# ETRX_RECU.net
KiCad netlist of a schematic drawn in Altium Designer
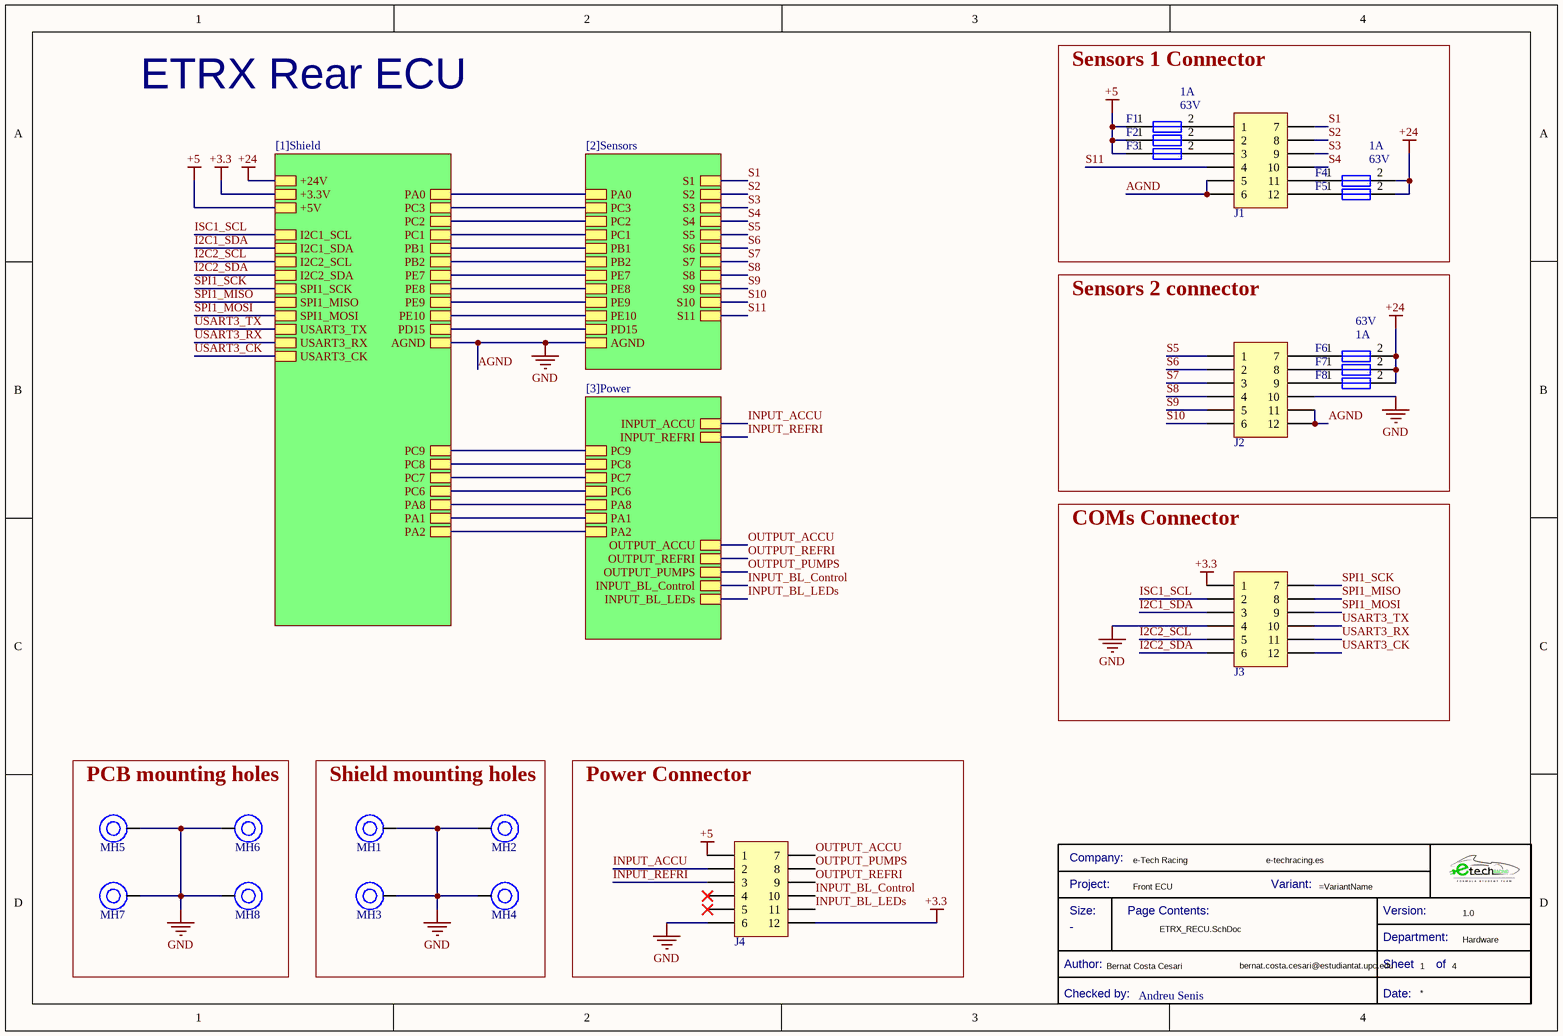
[diagram p0: ETRX_RECU.SchDoc]

(export (version "E")
  (design (tool "Eeschema 10.0.6"))
  (components
    (comp (ref "F1")
      (value "0437001.WRA")
      (footprint "Fuse_1206")
      (description "Fuse Chip Fast Acting 1A 63V SMD Solder Pad 1206 Ceramic T/R Automotive")
      (fields
        (field (name "MANUFACTURER") "Littelfuse")
        (field (name "CURRENT RATING") "1A")
        (field (name "VOLTAGE RATING (DC)") "63V")
        (field (name ".CREATOR") "DO")
      )
      (libsource (lib "Filter components") (part "Fuse_1A_63V_1206"))
    )
    (comp (ref "F2")
      (value "0437001.WRA")
      (footprint "Fuse_1206")
      (description "Fuse Chip Fast Acting 1A 63V SMD Solder Pad 1206 Ceramic T/R Automotive")
      (fields (field (name "MANUFACTURER") "Littelfuse") (field (name ".CREATOR") "DO"))
      (libsource (lib "Filter components") (part "Fuse_1A_63V_1206"))
    )
    (comp (ref "F3")
      (value "0437001.WRA")
      (footprint "Fuse_1206")
      (description "Fuse Chip Fast Acting 1A 63V SMD Solder Pad 1206 Ceramic T/R Automotive")
      (fields (field (name "MANUFACTURER") "Littelfuse") (field (name ".CREATOR") "DO"))
      (libsource (lib "Filter components") (part "Fuse_1A_63V_1206"))
    )
    (comp (ref "F4")
      (value "0437001.WRA")
      (footprint "Fuse_1206")
      (description "Fuse Chip Fast Acting 1A 63V SMD Solder Pad 1206 Ceramic T/R Automotive")
      (fields
        (field (name "MANUFACTURER") "Littelfuse")
        (field (name "CURRENT RATING") "1A")
        (field (name "VOLTAGE RATING (DC)") "63V")
        (field (name ".CREATOR") "DO")
      )
      (libsource (lib "Filter components") (part "Fuse_1A_63V_1206"))
    )
    (comp (ref "F5")
      (value "0437001.WRA")
      (footprint "Fuse_1206")
      (description "Fuse Chip Fast Acting 1A 63V SMD Solder Pad 1206 Ceramic T/R Automotive")
      (fields (field (name "MANUFACTURER") "Littelfuse") (field (name ".CREATOR") "DO"))
      (libsource (lib "Filter components") (part "Fuse_1A_63V_1206"))
    )
    (comp (ref "F6")
      (value "0437001.WRA")
      (footprint "Fuse_1206")
      (description "Fuse Chip Fast Acting 1A 63V SMD Solder Pad 1206 Ceramic T/R Automotive")
      (fields
        (field (name "MANUFACTURER") "Littelfuse")
        (field (name "CURRENT RATING") "1A")
        (field (name "VOLTAGE RATING (DC)") "63V")
        (field (name ".CREATOR") "DO")
      )
      (libsource (lib "Filter components") (part "Fuse_1A_63V_1206"))
    )
    (comp (ref "F7")
      (value "0437001.WRA")
      (footprint "Fuse_1206")
      (description "Fuse Chip Fast Acting 1A 63V SMD Solder Pad 1206 Ceramic T/R Automotive")
      (fields (field (name "MANUFACTURER") "Littelfuse") (field (name ".CREATOR") "DO"))
      (libsource (lib "Filter components") (part "Fuse_1A_63V_1206"))
    )
    (comp (ref "F8")
      (value "0437001.WRA")
      (footprint "Fuse_1206")
      (description "Fuse Chip Fast Acting 1A 63V SMD Solder Pad 1206 Ceramic T/R Automotive")
      (fields (field (name "MANUFACTURER") "Littelfuse") (field (name ".CREATOR") "DO"))
      (libsource (lib "Filter components") (part "Fuse_1A_63V_1206"))
    )
    (comp (ref "J1")
      (value "1053101112")
      (footprint "J_NanoFit_2x6_V")
      (libsource (lib "Electromechanical") (part "J_NanoFit_2x6_V"))
    )
    (comp (ref "J2")
      (value "1053101112")
      (footprint "J_NanoFit_2x6_V")
      (libsource (lib "Electromechanical") (part "J_NanoFit_2x6_V"))
    )
    (comp (ref "J3")
      (value "1053101112")
      (footprint "J_NanoFit_2x6_V")
      (libsource (lib "Electromechanical") (part "J_NanoFit_2x6_V"))
    )
    (comp (ref "J4")
      (value "1053101112")
      (footprint "J_NanoFit_2x6_V")
      (libsource (lib "Electromechanical") (part "J_NanoFit_2x6_V"))
    )
    (comp (ref "MH1")
      (value "Mounting_Hole_M3")
      (footprint "Mounting_Hole_M3")
      (libsource (lib "Electromechanical") (part "Mounting_Hole_M3"))
    )
    (comp (ref "MH2")
      (value "Mounting_Hole_M3")
      (footprint "Mounting_Hole_M3")
      (libsource (lib "Electromechanical") (part "Mounting_Hole_M3"))
    )
    (comp (ref "MH3")
      (value "Mounting_Hole_M3")
      (footprint "Mounting_Hole_M3")
      (libsource (lib "Electromechanical") (part "Mounting_Hole_M3"))
    )
    (comp (ref "MH4")
      (value "Mounting_Hole_M3")
      (footprint "Mounting_Hole_M3")
      (libsource (lib "Electromechanical") (part "Mounting_Hole_M3"))
    )
    (comp (ref "MH5")
      (value "Mounting_Hole_M4")
      (footprint "Mounting_Hole_M4")
      (libsource (lib "Electromechanical") (part "Mounting_Hole_M4"))
    )
    (comp (ref "MH6")
      (value "Mounting_Hole_M4")
      (footprint "Mounting_Hole_M4")
      (libsource (lib "Electromechanical") (part "Mounting_Hole_M4"))
    )
    (comp (ref "MH7")
      (value "Mounting_Hole_M4")
      (footprint "Mounting_Hole_M4")
      (libsource (lib "Electromechanical") (part "Mounting_Hole_M4"))
    )
    (comp (ref "MH8")
      (value "Mounting_Hole_M4")
      (footprint "Mounting_Hole_M4")
      (libsource (lib "Electromechanical") (part "Mounting_Hole_M4"))
    )
  )
  (nets
    (net (code "1") (name "+3.3") (class "Default")
      (node (ref "J3") (pin "1") (pinfunction "1_1") (pintype "passive"))
      (node (ref "J4") (pin "12") (pinfunction "12_12") (pintype "passive"))
    )
    (net (code "2") (name "+5") (class "Default")
      (node (ref "F1") (pin "1") (pinfunction "1_1") (pintype "passive"))
      (node (ref "F2") (pin "1") (pinfunction "1_1") (pintype "passive"))
      (node (ref "F3") (pin "1") (pinfunction "1_1") (pintype "passive"))
      (node (ref "J4") (pin "1") (pinfunction "1_1") (pintype "passive"))
    )
    (net (code "3") (name "+24") (class "Default")
      (node (ref "F4") (pin "2") (pinfunction "2_2") (pintype "passive"))
      (node (ref "F5") (pin "2") (pinfunction "2_2") (pintype "passive"))
      (node (ref "F6") (pin "2") (pinfunction "2_2") (pintype "passive"))
      (node (ref "F7") (pin "2") (pinfunction "2_2") (pintype "passive"))
      (node (ref "F8") (pin "2") (pinfunction "2_2") (pintype "passive"))
    )
    (net (code "4") (name "/I2C1_SDA") (class "Default")
      (node (ref "J3") (pin "3") (pinfunction "3_3") (pintype "passive"))
    )
    (net (code "5") (name "/I2C2_SCL") (class "Default")
      (node (ref "J3") (pin "5") (pinfunction "5_5") (pintype "passive"))
    )
    (net (code "6") (name "/I2C2_SDA") (class "Default")
      (node (ref "J3") (pin "6") (pinfunction "6_6") (pintype "passive"))
    )
    (net (code "7") (name "/INPUT_ACCU") (class "Default")
      (node (ref "J4") (pin "2") (pinfunction "2_2") (pintype "passive"))
    )
    (net (code "8") (name "/INPUT_BL_Control") (class "Default")
      (node (ref "J4") (pin "10") (pinfunction "10_10") (pintype "passive"))
    )
    (net (code "9") (name "/INPUT_BL_LEDs") (class "Default")
      (node (ref "J4") (pin "11") (pinfunction "11_11") (pintype "passive"))
    )
    (net (code "10") (name "/INPUT_REFRI") (class "Default")
      (node (ref "J4") (pin "3") (pinfunction "3_3") (pintype "passive"))
    )
    (net (code "11") (name "/ISC1_SCL") (class "Default")
      (node (ref "J3") (pin "2") (pinfunction "2_2") (pintype "passive"))
    )
    (net (code "12") (name "/OUTPUT_ACCU") (class "Default")
      (node (ref "J4") (pin "7") (pinfunction "7_7") (pintype "passive"))
    )
    (net (code "13") (name "/OUTPUT_PUMPS") (class "Default")
      (node (ref "J4") (pin "8") (pinfunction "8_8") (pintype "passive"))
    )
    (net (code "14") (name "/OUTPUT_REFRI") (class "Default")
      (node (ref "J4") (pin "9") (pinfunction "9_9") (pintype "passive"))
    )
    (net (code "33") (name "/S1") (class "Default")
      (node (ref "J1") (pin "7") (pinfunction "7_7") (pintype "passive"))
    )
    (net (code "34") (name "/S2") (class "Default")
      (node (ref "J1") (pin "8") (pinfunction "8_8") (pintype "passive"))
    )
    (net (code "35") (name "/S3") (class "Default")
      (node (ref "J1") (pin "9") (pinfunction "9_9") (pintype "passive"))
    )
    (net (code "36") (name "/S4") (class "Default")
      (node (ref "J1") (pin "10") (pinfunction "10_10") (pintype "passive"))
    )
    (net (code "37") (name "/S5") (class "Default")
      (node (ref "J2") (pin "1") (pinfunction "1_1") (pintype "passive"))
    )
    (net (code "38") (name "/S6") (class "Default")
      (node (ref "J2") (pin "2") (pinfunction "2_2") (pintype "passive"))
    )
    (net (code "39") (name "/S7") (class "Default")
      (node (ref "J2") (pin "3") (pinfunction "3_3") (pintype "passive"))
    )
    (net (code "40") (name "/S8") (class "Default")
      (node (ref "J2") (pin "4") (pinfunction "4_4") (pintype "passive"))
    )
    (net (code "41") (name "/S9") (class "Default")
      (node (ref "J2") (pin "5") (pinfunction "5_5") (pintype "passive"))
    )
    (net (code "42") (name "/S10") (class "Default")
      (node (ref "J2") (pin "6") (pinfunction "6_6") (pintype "passive"))
    )
    (net (code "43") (name "/S11") (class "Default")
      (node (ref "J1") (pin "4") (pinfunction "4_4") (pintype "passive"))
    )
    (net (code "44") (name "/SPI1_MISO") (class "Default")
      (node (ref "J3") (pin "8") (pinfunction "8_8") (pintype "passive"))
    )
    (net (code "45") (name "/SPI1_MOSI") (class "Default")
      (node (ref "J3") (pin "9") (pinfunction "9_9") (pintype "passive"))
    )
    (net (code "46") (name "/SPI1_SCK") (class "Default")
      (node (ref "J3") (pin "7") (pinfunction "7_7") (pintype "passive"))
    )
    (net (code "47") (name "/USART3_CK") (class "Default")
      (node (ref "J3") (pin "12") (pinfunction "12_12") (pintype "passive"))
    )
    (net (code "48") (name "/USART3_RX") (class "Default")
      (node (ref "J3") (pin "11") (pinfunction "11_11") (pintype "passive"))
    )
    (net (code "49") (name "/USART3_TX") (class "Default")
      (node (ref "J3") (pin "10") (pinfunction "10_10") (pintype "passive"))
    )
    (net (code "50") (name "GND") (class "Default")
      (node (ref "J1") (pin "5") (pinfunction "5_5") (pintype "passive"))
      (node (ref "J1") (pin "6") (pinfunction "6_6") (pintype "passive"))
      (node (ref "J2") (pin "10") (pinfunction "10_10") (pintype "passive"))
      (node (ref "J2") (pin "11") (pinfunction "11_11") (pintype "passive"))
      (node (ref "J2") (pin "12") (pinfunction "12_12") (pintype "passive"))
      (node (ref "J3") (pin "4") (pinfunction "4_4") (pintype "passive"))
      (node (ref "J4") (pin "6") (pinfunction "6_6") (pintype "passive"))
      (node (ref "MH1") (pin "1") (pinfunction "1_1") (pintype "passive"))
      (node (ref "MH2") (pin "1") (pinfunction "1_1") (pintype "passive"))
      (node (ref "MH3") (pin "1") (pinfunction "1_1") (pintype "passive"))
      (node (ref "MH4") (pin "1") (pinfunction "1_1") (pintype "passive"))
      (node (ref "MH5") (pin "1") (pinfunction "1_1") (pintype "passive"))
      (node (ref "MH6") (pin "1") (pinfunction "1_1") (pintype "passive"))
      (node (ref "MH7") (pin "1") (pinfunction "1_1") (pintype "passive"))
      (node (ref "MH8") (pin "1") (pinfunction "1_1") (pintype "passive"))
    )
    (net (code "51") (name "Net-(F1-Pad2)") (class "Default")
      (node (ref "F1") (pin "2") (pinfunction "2_2") (pintype "passive"))
      (node (ref "J1") (pin "1") (pinfunction "1_1") (pintype "passive"))
    )
    (net (code "52") (name "Net-(F2-Pad2)") (class "Default")
      (node (ref "F2") (pin "2") (pinfunction "2_2") (pintype "passive"))
      (node (ref "J1") (pin "2") (pinfunction "2_2") (pintype "passive"))
    )
    (net (code "53") (name "Net-(F3-Pad2)") (class "Default")
      (node (ref "F3") (pin "2") (pinfunction "2_2") (pintype "passive"))
      (node (ref "J1") (pin "3") (pinfunction "3_3") (pintype "passive"))
    )
    (net (code "54") (name "Net-(F4-Pad1)") (class "Default")
      (node (ref "F4") (pin "1") (pinfunction "1_1") (pintype "passive"))
      (node (ref "J1") (pin "11") (pinfunction "11_11") (pintype "passive"))
    )
    (net (code "55") (name "Net-(F5-Pad1)") (class "Default")
      (node (ref "F5") (pin "1") (pinfunction "1_1") (pintype "passive"))
      (node (ref "J1") (pin "12") (pinfunction "12_12") (pintype "passive"))
    )
    (net (code "56") (name "Net-(F6-Pad1)") (class "Default")
      (node (ref "F6") (pin "1") (pinfunction "1_1") (pintype "passive"))
      (node (ref "J2") (pin "7") (pinfunction "7_7") (pintype "passive"))
    )
    (net (code "57") (name "Net-(F7-Pad1)") (class "Default")
      (node (ref "F7") (pin "1") (pinfunction "1_1") (pintype "passive"))
      (node (ref "J2") (pin "8") (pinfunction "8_8") (pintype "passive"))
    )
    (net (code "58") (name "Net-(F8-Pad1)") (class "Default")
      (node (ref "F8") (pin "1") (pinfunction "1_1") (pintype "passive"))
      (node (ref "J2") (pin "9") (pinfunction "9_9") (pintype "passive"))
    )
    (net (code "59") (name "unconnected-(J4-Pad4)") (class "Default")
      (node (ref "J4") (pin "4") (pinfunction "4_4") (pintype "passive+no_connect"))
    )
    (net (code "60") (name "unconnected-(J4-Pad5)") (class "Default")
      (node (ref "J4") (pin "5") (pinfunction "5_5") (pintype "passive+no_connect"))
    )
  )
)
